# InterfaceConfiguracao.net
KiCad netlist of a schematic drawn in Altium Designer
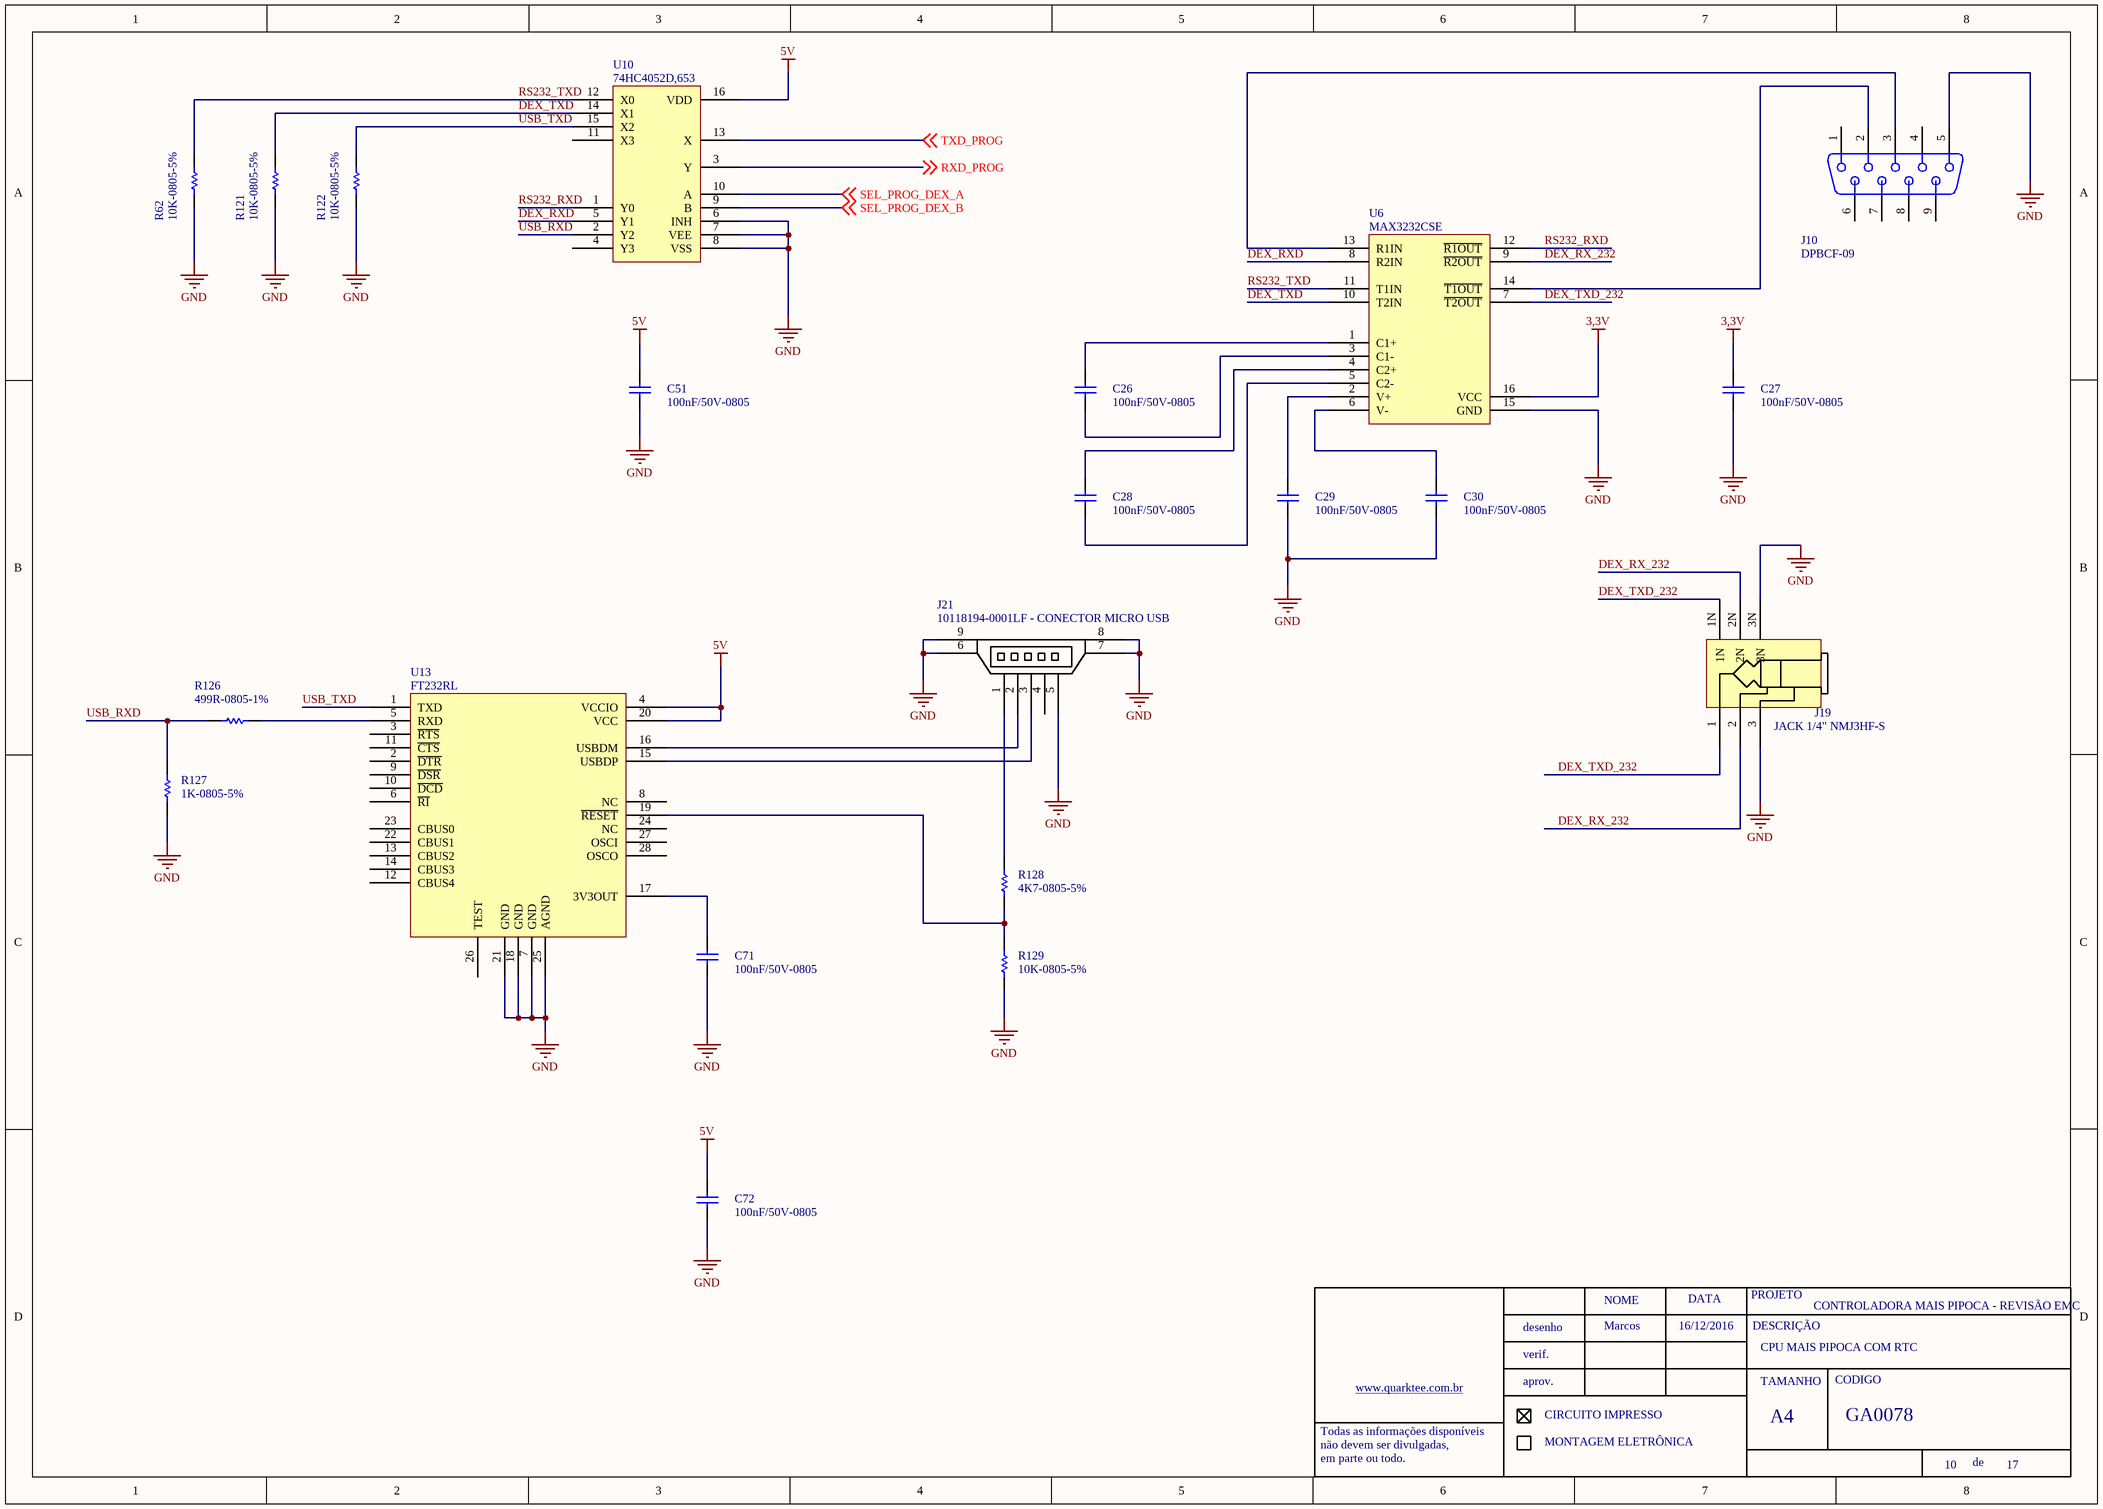
[diagram p0: InterfaceConfiguracao.SchDoc]

(export (version "E")
  (design (tool "Eeschema 10.0.6"))
  (components
    (comp (ref "C26")
      (value "100nF/50V-0805")
      (footprint "0805-REVISADO ONDA")
      (description "100nF/50-0805-NPO")
      (libsource (lib "AquinoLib") (part "100nF/50-0805-NPO"))
    )
    (comp (ref "C27")
      (value "100nF/50V-0805")
      (footprint "0805-REVISADO ONDA")
      (description "100nF/50-0805-NPO")
      (libsource (lib "AquinoLib") (part "100nF/50-0805-NPO"))
    )
    (comp (ref "C28")
      (value "100nF/50V-0805")
      (footprint "0805-REVISADO ONDA")
      (description "100nF/50-0805-NPO")
      (libsource (lib "AquinoLib") (part "100nF/50-0805-NPO"))
    )
    (comp (ref "C29")
      (value "100nF/50V-0805")
      (footprint "0805-REVISADO ONDA")
      (description "100nF/50-0805-NPO")
      (libsource (lib "AquinoLib") (part "100nF/50-0805-NPO"))
    )
    (comp (ref "C30")
      (value "100nF/50V-0805")
      (footprint "0805-REVISADO ONDA")
      (description "100nF/50-0805-NPO")
      (libsource (lib "AquinoLib") (part "100nF/50-0805-NPO"))
    )
    (comp (ref "C51")
      (value "100nF/50V-0805")
      (footprint "0805-REVISADO ONDA")
      (libsource (lib "AquinoLib") (part "100nF/50-0805-NPO"))
    )
    (comp (ref "C71")
      (value "100nF/50V-0805")
      (footprint "0805-REVISADO ONDA")
      (libsource (lib "AquinoLib") (part "100nF/50-0805-NPO"))
    )
    (comp (ref "C72")
      (value "100nF/50V-0805")
      (footprint "0805-REVISADO ONDA")
      (libsource (lib "AquinoLib") (part "100nF/50-0805-NPO"))
    )
    (comp (ref "J10")
      (value "DPBCF-09")
      (footprint "DB9-FÊMEA MONTAGEM EM PCI 180")
      (description "DBPCF-09")
      (libsource (lib "ChaveDigital3") (part "DB-9 - FÊMEA 180º MONTAGEM EM PCI"))
    )
    (comp (ref "J19")
      (value "JACK 1/4\" NMJ3HF-S")
      (description "NMJ3HF-S")
      (libsource (lib "AquinoLib") (part "NMJ3HF-S"))
    )
    (comp (ref "J21")
      (value "10118194-0001LF - CONECTOR MICRO USB")
      (libsource (lib "AquinoLib") (part "MINI_USB"))
    )
    (comp (ref "R62")
      (value "10K-0805-5%")
      (footprint "0805-REVISADO ONDA")
      (libsource (lib "AquinoLib") (part "10K-0805-5%"))
    )
    (comp (ref "R121")
      (value "10K-0805-5%")
      (footprint "0805-REVISADO ONDA")
      (libsource (lib "AquinoLib") (part "10K-0805-5%"))
    )
    (comp (ref "R122")
      (value "10K-0805-5%")
      (footprint "0805-REVISADO ONDA")
      (libsource (lib "AquinoLib") (part "10K-0805-5%"))
    )
    (comp (ref "R126")
      (value "499R-0805-1%")
      (footprint "0805-REVISADO ONDA")
      (description "1K-0805-5%")
      (libsource (lib "AquinoLib") (part "1K-0805-5%"))
    )
    (comp (ref "R127")
      (value "1K-0805-5%")
      (footprint "0805-REVISADO ONDA")
      (libsource (lib "AquinoLib") (part "1K-0805-5%"))
    )
    (comp (ref "R128")
      (value "4K7-0805-5%")
      (footprint "0805-REVISADO ONDA")
      (description "10K-0805-5%")
      (libsource (lib "AquinoLib") (part "10K-0805-5%"))
    )
    (comp (ref "R129")
      (value "10K-0805-5%")
      (footprint "0805-REVISADO ONDA")
      (libsource (lib "AquinoLib") (part "10K-0805-5%"))
    )
    (comp (ref "U6")
      (value "MAX3232CSE")
      (footprint "SOIC 16 PINOS")
      (libsource (lib "ChaveDigital3") (part "MAX3232CSE"))
    )
    (comp (ref "U10") (value "74HC4052D,653") (libsource (lib "AquinoLib") (part "CD74HC4052PWR")))
    (comp (ref "U13") (value "FT232RL") (libsource (lib "AquinoLib") (part "FT232RL")))
  )
  (nets
    (net (code "1") (name "/DEX_RXD") (class "Default")
      (node (ref "U10") (pin "5") (pinfunction "Y1_5") (pintype "passive"))
      (node (ref "U6") (pin "8") (pinfunction "R2IN_8") (pintype "passive"))
    )
    (net (code "2") (name "/DEX_RX_232") (class "Default")
      (node (ref "J19") (pin "2") (pinfunction "2_2") (pintype "passive"))
      (node (ref "J19") (pin "2N") (pinfunction "2N_2N") (pintype "passive"))
      (node (ref "U6") (pin "9") (pinfunction "~{R2OUT}_9") (pintype "passive"))
    )
    (net (code "3") (name "/DEX_TXD") (class "Default")
      (node (ref "R121") (pin "2") (pinfunction "2_2") (pintype "passive"))
      (node (ref "U10") (pin "14") (pinfunction "X1_14") (pintype "passive"))
      (node (ref "U6") (pin "10") (pinfunction "T2IN_10") (pintype "passive"))
    )
    (net (code "4") (name "/DEX_TXD_232") (class "Default")
      (node (ref "J19") (pin "1") (pinfunction "1_1") (pintype "passive"))
      (node (ref "J19") (pin "1N") (pinfunction "1N_1N") (pintype "passive"))
      (node (ref "U6") (pin "7") (pinfunction "~{T2OUT}_7") (pintype "passive"))
    )
    (net (code "5") (name "/RS232_RXD") (class "Default")
      (node (ref "U10") (pin "1") (pinfunction "Y0_1") (pintype "passive"))
      (node (ref "U6") (pin "12") (pinfunction "~{R1OUT}_12") (pintype "passive"))
    )
    (net (code "6") (name "/RS232_TXD") (class "Default")
      (node (ref "R62") (pin "2") (pinfunction "2_2") (pintype "passive"))
      (node (ref "U10") (pin "12") (pinfunction "X0_12") (pintype "passive"))
      (node (ref "U6") (pin "11") (pinfunction "T1IN_11") (pintype "passive"))
    )
    (net (code "7") (name "/USB_RXD") (class "Default")
      (node (ref "R126") (pin "1") (pinfunction "1_1") (pintype "passive"))
      (node (ref "R127") (pin "2") (pinfunction "2_2") (pintype "passive"))
      (node (ref "U10") (pin "2") (pinfunction "Y2_2") (pintype "passive"))
    )
    (net (code "8") (name "/USB_TXD") (class "Default")
      (node (ref "R122") (pin "2") (pinfunction "2_2") (pintype "passive"))
      (node (ref "U10") (pin "15") (pinfunction "X2_15") (pintype "passive"))
      (node (ref "U13") (pin "1") (pinfunction "TXD_1") (pintype "passive"))
    )
    (net (code "9") (name "3,3V") (class "Default")
      (node (ref "C27") (pin "2") (pinfunction "2_2") (pintype "passive"))
      (node (ref "U6") (pin "16") (pinfunction "VCC_16") (pintype "passive"))
    )
    (net (code "10") (name "5V") (class "Default")
      (node (ref "C51") (pin "2") (pinfunction "2_2") (pintype "passive"))
      (node (ref "C72") (pin "2") (pinfunction "2_2") (pintype "passive"))
      (node (ref "U10") (pin "16") (pinfunction "VDD_16") (pintype "passive"))
      (node (ref "U13") (pin "20") (pinfunction "VCC_20") (pintype "passive"))
      (node (ref "U13") (pin "4") (pinfunction "VCCIO_4") (pintype "passive"))
    )
    (net (code "11") (name "GND") (class "Default")
      (node (ref "C27") (pin "1") (pinfunction "1_1") (pintype "passive"))
      (node (ref "C29") (pin "1") (pinfunction "1_1") (pintype "passive"))
      (node (ref "C30") (pin "1") (pinfunction "1_1") (pintype "passive"))
      (node (ref "C51") (pin "1") (pinfunction "1_1") (pintype "passive"))
      (node (ref "C71") (pin "1") (pinfunction "1_1") (pintype "passive"))
      (node (ref "C72") (pin "1") (pinfunction "1_1") (pintype "passive"))
      (node (ref "J10") (pin "5") (pinfunction "5_5") (pintype "passive"))
      (node (ref "J19") (pin "3") (pinfunction "3_3") (pintype "passive"))
      (node (ref "J19") (pin "3N") (pinfunction "3N_3N") (pintype "passive"))
      (node (ref "J21") (pin "5") (pinfunction "5_5") (pintype "passive"))
      (node (ref "J21") (pin "6") (pinfunction "6_6") (pintype "passive"))
      (node (ref "J21") (pin "7") (pinfunction "7_7") (pintype "passive"))
      (node (ref "J21") (pin "8") (pinfunction "8_8") (pintype "passive"))
      (node (ref "J21") (pin "9") (pinfunction "9_9") (pintype "passive"))
      (node (ref "R121") (pin "1") (pinfunction "1_1") (pintype "passive"))
      (node (ref "R122") (pin "1") (pinfunction "1_1") (pintype "passive"))
      (node (ref "R127") (pin "1") (pinfunction "1_1") (pintype "passive"))
      (node (ref "R129") (pin "1") (pinfunction "1_1") (pintype "passive"))
      (node (ref "R62") (pin "1") (pinfunction "1_1") (pintype "passive"))
      (node (ref "U10") (pin "6") (pinfunction "INH_6") (pintype "passive"))
      (node (ref "U10") (pin "7") (pinfunction "VEE_7") (pintype "passive"))
      (node (ref "U10") (pin "8") (pinfunction "VSS_8") (pintype "passive"))
      (node (ref "U13") (pin "18") (pinfunction "GND_18") (pintype "passive"))
      (node (ref "U13") (pin "21") (pinfunction "GND_21") (pintype "passive"))
      (node (ref "U13") (pin "25") (pinfunction "AGND_25") (pintype "passive"))
      (node (ref "U13") (pin "7") (pinfunction "GND_7") (pintype "passive"))
      (node (ref "U6") (pin "15") (pinfunction "GND_15") (pintype "passive"))
    )
    (net (code "12") (name "Net-(J21-Pad1)") (class "Default")
      (node (ref "J21") (pin "1") (pinfunction "1_1") (pintype "passive"))
      (node (ref "R128") (pin "2") (pinfunction "2_2") (pintype "passive"))
    )
    (net (code "13") (name "Net-(U6-C1+)") (class "Default")
      (node (ref "C26") (pin "2") (pinfunction "2_2") (pintype "passive"))
      (node (ref "U6") (pin "1") (pinfunction "C1+_1") (pintype "passive"))
    )
    (net (code "14") (name "Net-(U6-C1-)") (class "Default")
      (node (ref "C26") (pin "1") (pinfunction "1_1") (pintype "passive"))
      (node (ref "U6") (pin "3") (pinfunction "C1-_3") (pintype "passive"))
    )
    (net (code "15") (name "Net-(U6-C2+)") (class "Default")
      (node (ref "C28") (pin "2") (pinfunction "2_2") (pintype "passive"))
      (node (ref "U6") (pin "4") (pinfunction "C2+_4") (pintype "passive"))
    )
    (net (code "16") (name "Net-(U6-C2-)") (class "Default")
      (node (ref "C28") (pin "1") (pinfunction "1_1") (pintype "passive"))
      (node (ref "U6") (pin "5") (pinfunction "C2-_5") (pintype "passive"))
    )
    (net (code "17") (name "Net-(U6-R1IN)") (class "Default")
      (node (ref "J10") (pin "3") (pinfunction "3_3") (pintype "passive"))
      (node (ref "U6") (pin "13") (pinfunction "R1IN_13") (pintype "passive"))
    )
    (net (code "18") (name "Net-(U6-V+)") (class "Default")
      (node (ref "C29") (pin "2") (pinfunction "2_2") (pintype "passive"))
      (node (ref "U6") (pin "2") (pinfunction "V+_2") (pintype "passive"))
    )
    (net (code "19") (name "Net-(U6-V-)") (class "Default")
      (node (ref "C30") (pin "2") (pinfunction "2_2") (pintype "passive"))
      (node (ref "U6") (pin "6") (pinfunction "V-_6") (pintype "passive"))
    )
    (net (code "20") (name "Net-(U6-~{T1OUT})") (class "Default")
      (node (ref "J10") (pin "2") (pinfunction "2_2") (pintype "passive"))
      (node (ref "U6") (pin "14") (pinfunction "~{T1OUT}_14") (pintype "passive"))
    )
    (net (code "21") (name "Net-(U13-3V3OUT)") (class "Default")
      (node (ref "C71") (pin "2") (pinfunction "2_2") (pintype "passive"))
      (node (ref "U13") (pin "17") (pinfunction "3V3OUT_17") (pintype "passive"))
    )
    (net (code "22") (name "Net-(U13-RXD)") (class "Default")
      (node (ref "R126") (pin "2") (pinfunction "2_2") (pintype "passive"))
      (node (ref "U13") (pin "5") (pinfunction "RXD_5") (pintype "passive"))
    )
    (net (code "23") (name "Net-(U13-USBDM)") (class "Default")
      (node (ref "J21") (pin "2") (pinfunction "2_2") (pintype "passive"))
      (node (ref "U13") (pin "16") (pinfunction "USBDM_16") (pintype "passive"))
    )
    (net (code "24") (name "Net-(U13-USBDP)") (class "Default")
      (node (ref "J21") (pin "3") (pinfunction "3_3") (pintype "passive"))
      (node (ref "U13") (pin "15") (pinfunction "USBDP_15") (pintype "passive"))
    )
    (net (code "25") (name "Net-(U13-~{RESET})") (class "Default")
      (node (ref "R128") (pin "1") (pinfunction "1_1") (pintype "passive"))
      (node (ref "R129") (pin "2") (pinfunction "2_2") (pintype "passive"))
      (node (ref "U13") (pin "19") (pinfunction "~{RESET}_19") (pintype "passive"))
    )
    (net (code "26") (name "RXD_PROG") (class "Default")
      (node (ref "U10") (pin "3") (pinfunction "Y_3") (pintype "passive"))
    )
    (net (code "27") (name "SEL_PROG_DEX_A") (class "Default")
      (node (ref "U10") (pin "10") (pinfunction "A_10") (pintype "passive"))
    )
    (net (code "28") (name "SEL_PROG_DEX_B") (class "Default")
      (node (ref "U10") (pin "9") (pinfunction "B_9") (pintype "passive"))
    )
    (net (code "29") (name "TXD_PROG") (class "Default")
      (node (ref "U10") (pin "13") (pinfunction "X_13") (pintype "passive"))
    )
    (net (code "30") (name "unconnected-(J10-Pad1)") (class "Default")
      (node (ref "J10") (pin "1") (pinfunction "1_1") (pintype "passive"))
    )
    (net (code "31") (name "unconnected-(J10-Pad4)") (class "Default")
      (node (ref "J10") (pin "4") (pinfunction "4_4") (pintype "passive"))
    )
    (net (code "32") (name "unconnected-(J10-Pad6)") (class "Default")
      (node (ref "J10") (pin "6") (pinfunction "6_6") (pintype "passive"))
    )
    (net (code "33") (name "unconnected-(J10-Pad7)") (class "Default")
      (node (ref "J10") (pin "7") (pinfunction "7_7") (pintype "passive"))
    )
    (net (code "34") (name "unconnected-(J10-Pad8)") (class "Default")
      (node (ref "J10") (pin "8") (pinfunction "8_8") (pintype "passive"))
    )
    (net (code "35") (name "unconnected-(J10-Pad9)") (class "Default")
      (node (ref "J10") (pin "9") (pinfunction "9_9") (pintype "passive"))
    )
    (net (code "36") (name "unconnected-(J21-Pad4)") (class "Default")
      (node (ref "J21") (pin "4") (pinfunction "4_4") (pintype "passive"))
    )
    (net (code "37") (name "unconnected-(U10-X3-Pad11)") (class "Default")
      (node (ref "U10") (pin "11") (pinfunction "X3_11") (pintype "passive"))
    )
    (net (code "38") (name "unconnected-(U10-Y3-Pad4)") (class "Default")
      (node (ref "U10") (pin "4") (pinfunction "Y3_4") (pintype "passive"))
    )
    (net (code "39") (name "unconnected-(U13-CBUS0-Pad23)") (class "Default")
      (node (ref "U13") (pin "23") (pinfunction "CBUS0_23") (pintype "passive"))
    )
    (net (code "40") (name "unconnected-(U13-CBUS1-Pad22)") (class "Default")
      (node (ref "U13") (pin "22") (pinfunction "CBUS1_22") (pintype "passive"))
    )
    (net (code "41") (name "unconnected-(U13-CBUS2-Pad13)") (class "Default")
      (node (ref "U13") (pin "13") (pinfunction "CBUS2_13") (pintype "passive"))
    )
    (net (code "42") (name "unconnected-(U13-CBUS3-Pad14)") (class "Default")
      (node (ref "U13") (pin "14") (pinfunction "CBUS3_14") (pintype "passive"))
    )
    (net (code "43") (name "unconnected-(U13-CBUS4-Pad12)") (class "Default")
      (node (ref "U13") (pin "12") (pinfunction "CBUS4_12") (pintype "passive"))
    )
    (net (code "44") (name "unconnected-(U13-NC-Pad8)") (class "Default")
      (node (ref "U13") (pin "8") (pinfunction "NC_8") (pintype "passive"))
    )
    (net (code "45") (name "unconnected-(U13-NC-Pad24)") (class "Default")
      (node (ref "U13") (pin "24") (pinfunction "NC_24") (pintype "passive"))
    )
    (net (code "46") (name "unconnected-(U13-OSCI-Pad27)") (class "Default")
      (node (ref "U13") (pin "27") (pinfunction "OSCI_27") (pintype "passive"))
    )
    (net (code "47") (name "unconnected-(U13-OSCO-Pad28)") (class "Default")
      (node (ref "U13") (pin "28") (pinfunction "OSCO_28") (pintype "passive"))
    )
    (net (code "48") (name "unconnected-(U13-TEST-Pad26)") (class "Default")
      (node (ref "U13") (pin "26") (pinfunction "TEST_26") (pintype "passive"))
    )
    (net (code "49") (name "unconnected-(U13-~{CTS}-Pad11)") (class "Default")
      (node (ref "U13") (pin "11") (pinfunction "~{CTS}_11") (pintype "passive"))
    )
    (net (code "50") (name "unconnected-(U13-~{DCD}-Pad10)") (class "Default")
      (node (ref "U13") (pin "10") (pinfunction "~{DCD}_10") (pintype "passive"))
    )
    (net (code "51") (name "unconnected-(U13-~{DSR}-Pad9)") (class "Default")
      (node (ref "U13") (pin "9") (pinfunction "~{DSR}_9") (pintype "passive"))
    )
    (net (code "52") (name "unconnected-(U13-~{DTR}-Pad2)") (class "Default")
      (node (ref "U13") (pin "2") (pinfunction "~{DTR}_2") (pintype "passive"))
    )
    (net (code "53") (name "unconnected-(U13-~{RI}-Pad6)") (class "Default")
      (node (ref "U13") (pin "6") (pinfunction "~{RI}_6") (pintype "passive"))
    )
    (net (code "54") (name "unconnected-(U13-~{RTS}-Pad3)") (class "Default")
      (node (ref "U13") (pin "3") (pinfunction "~{RTS}_3") (pintype "passive"))
    )
  )
)
